# FMC_HPC_400.net
KiCad netlist of a schematic drawn in Altium Designer
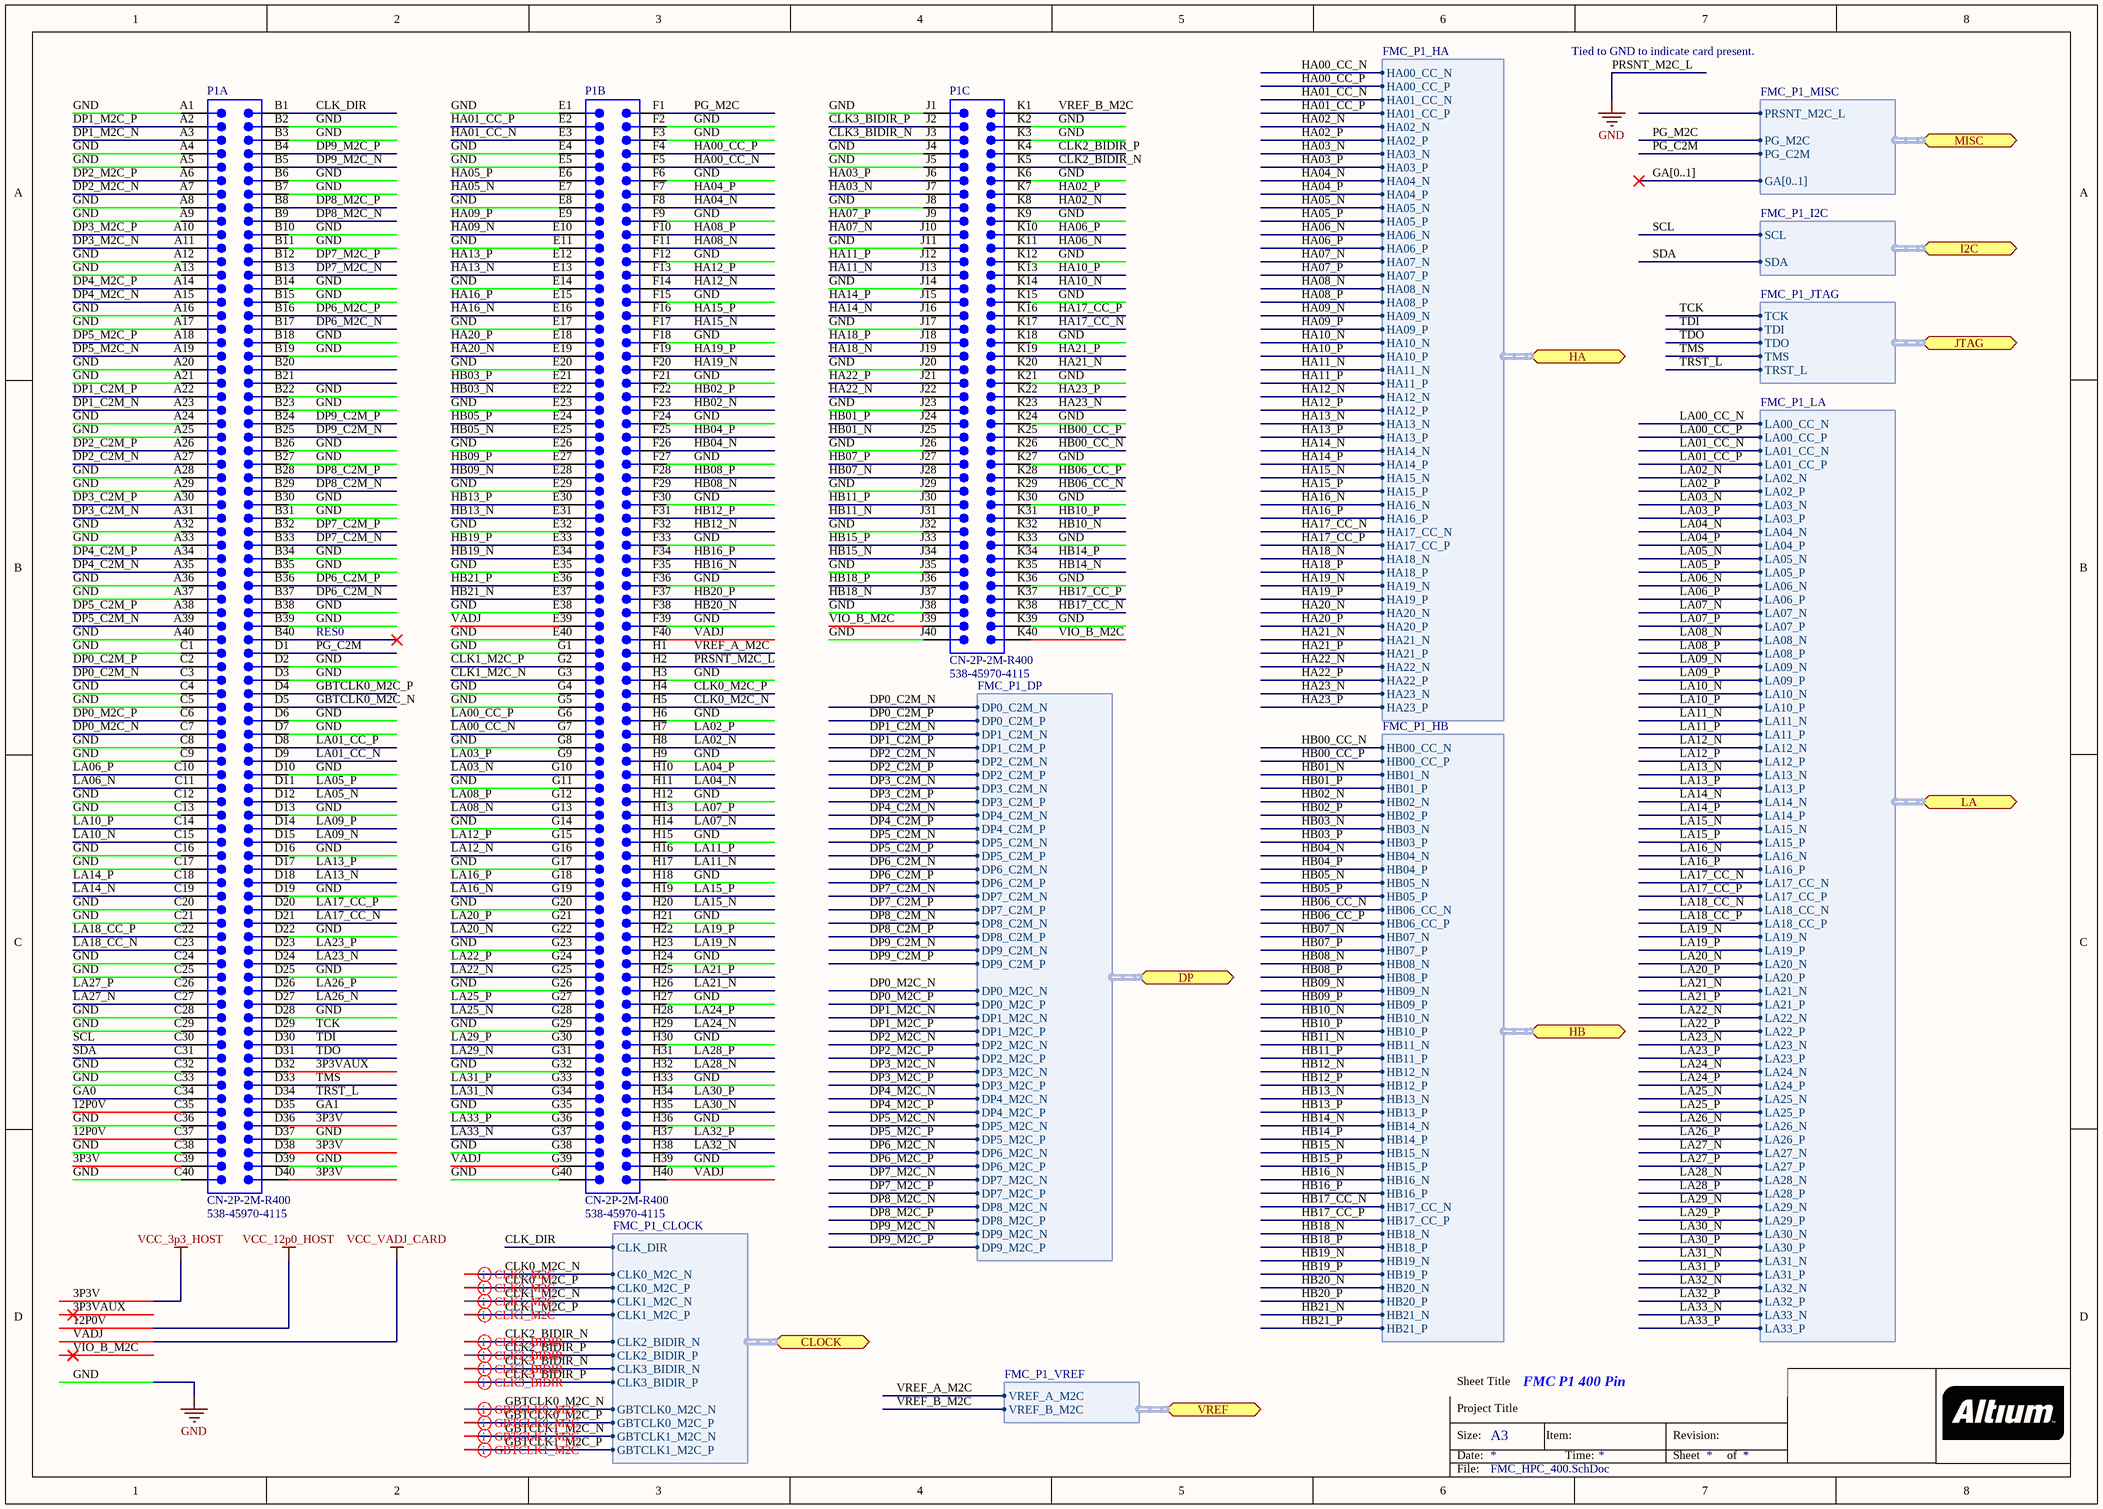
[diagram p0: FMC_HPC_400.SchDoc]

(export (version "E")
  (design (tool "Eeschema 10.0.6"))
  (components
    (comp (ref "P1")
      (value "CN-2P-2M-R400")
      (footprint "BTB-SM1-27-2V400M")
      (description "Board-to-Board Connector, Vertical, 10-Row, Pitch 1.27mm, 400-Position")
      (fields
        (field (name "MANUFACTURER") "Molex")
        (field (name "MANUFACTURER PART NUMBER") "45970-4115")
        (field (name "SUPPLIER PART NUMBER 1") "538-45970-4115")
      )
      (libsource (lib "RNG_Parts") (part "CN-2P-2M-R400"))
    )
  )
  (nets
    (net (code "10") (name "/3P3VAUX") (class "Default")
      (node (ref "P1") (pin "D32") (pinfunction "D32_D32") (pintype "passive+no_connect"))
    )
    (net (code "11") (name "/CLK0_M2C_N") (class "Default")
      (node (ref "P1") (pin "H5") (pinfunction "H5_H5") (pintype "passive"))
    )
    (net (code "12") (name "/CLK0_M2C_P") (class "Default")
      (node (ref "P1") (pin "H4") (pinfunction "H4_H4") (pintype "passive"))
    )
    (net (code "13") (name "/CLK1_M2C_N") (class "Default")
      (node (ref "P1") (pin "G3") (pinfunction "G3_G3") (pintype "passive"))
    )
    (net (code "14") (name "/CLK1_M2C_P") (class "Default")
      (node (ref "P1") (pin "G2") (pinfunction "G2_G2") (pintype "passive"))
    )
    (net (code "15") (name "/CLK2_BIDIR_N") (class "Default")
      (node (ref "P1") (pin "K5") (pinfunction "K5_K5") (pintype "passive"))
    )
    (net (code "16") (name "/CLK2_BIDIR_P") (class "Default")
      (node (ref "P1") (pin "K4") (pinfunction "K4_K4") (pintype "passive"))
    )
    (net (code "17") (name "/CLK3_BIDIR_N") (class "Default")
      (node (ref "P1") (pin "J3") (pinfunction "J3_J3") (pintype "passive"))
    )
    (net (code "18") (name "/CLK3_BIDIR_P") (class "Default")
      (node (ref "P1") (pin "J2") (pinfunction "J2_J2") (pintype "passive"))
    )
    (net (code "19") (name "/CLK_DIR") (class "Default")
      (node (ref "P1") (pin "B1") (pinfunction "B1_B1") (pintype "passive"))
    )
    (net (code "20") (name "/DP0_C2M_N") (class "Default")
      (node (ref "P1") (pin "C3") (pinfunction "C3_C3") (pintype "passive"))
    )
    (net (code "21") (name "/DP0_C2M_P") (class "Default")
      (node (ref "P1") (pin "C2") (pinfunction "C2_C2") (pintype "passive"))
    )
    (net (code "22") (name "/DP0_M2C_N") (class "Default")
      (node (ref "P1") (pin "C7") (pinfunction "C7_C7") (pintype "passive"))
    )
    (net (code "23") (name "/DP0_M2C_P") (class "Default")
      (node (ref "P1") (pin "C6") (pinfunction "C6_C6") (pintype "passive"))
    )
    (net (code "24") (name "/DP1_C2M_N") (class "Default")
      (node (ref "P1") (pin "A23") (pinfunction "A23_A23") (pintype "passive"))
    )
    (net (code "25") (name "/DP1_C2M_P") (class "Default")
      (node (ref "P1") (pin "A22") (pinfunction "A22_A22") (pintype "passive"))
    )
    (net (code "26") (name "/DP1_M2C_N") (class "Default")
      (node (ref "P1") (pin "A3") (pinfunction "A3_A3") (pintype "passive"))
    )
    (net (code "27") (name "/DP1_M2C_P") (class "Default")
      (node (ref "P1") (pin "A2") (pinfunction "A2_A2") (pintype "passive"))
    )
    (net (code "28") (name "/DP2_C2M_N") (class "Default")
      (node (ref "P1") (pin "A27") (pinfunction "A27_A27") (pintype "passive"))
    )
    (net (code "29") (name "/DP2_C2M_P") (class "Default")
      (node (ref "P1") (pin "A26") (pinfunction "A26_A26") (pintype "passive"))
    )
    (net (code "30") (name "/DP2_M2C_N") (class "Default")
      (node (ref "P1") (pin "A7") (pinfunction "A7_A7") (pintype "passive"))
    )
    (net (code "31") (name "/DP2_M2C_P") (class "Default")
      (node (ref "P1") (pin "A6") (pinfunction "A6_A6") (pintype "passive"))
    )
    (net (code "32") (name "/DP3_C2M_N") (class "Default")
      (node (ref "P1") (pin "A31") (pinfunction "A31_A31") (pintype "passive"))
    )
    (net (code "33") (name "/DP3_C2M_P") (class "Default")
      (node (ref "P1") (pin "A30") (pinfunction "A30_A30") (pintype "passive"))
    )
    (net (code "34") (name "/DP3_M2C_N") (class "Default")
      (node (ref "P1") (pin "A11") (pinfunction "A11_A11") (pintype "passive"))
    )
    (net (code "35") (name "/DP3_M2C_P") (class "Default")
      (node (ref "P1") (pin "A10") (pinfunction "A10_A10") (pintype "passive"))
    )
    (net (code "36") (name "/DP4_C2M_N") (class "Default")
      (node (ref "P1") (pin "A35") (pinfunction "A35_A35") (pintype "passive"))
    )
    (net (code "37") (name "/DP4_C2M_P") (class "Default")
      (node (ref "P1") (pin "A34") (pinfunction "A34_A34") (pintype "passive"))
    )
    (net (code "38") (name "/DP4_M2C_N") (class "Default")
      (node (ref "P1") (pin "A15") (pinfunction "A15_A15") (pintype "passive"))
    )
    (net (code "39") (name "/DP4_M2C_P") (class "Default")
      (node (ref "P1") (pin "A14") (pinfunction "A14_A14") (pintype "passive"))
    )
    (net (code "40") (name "/DP5_C2M_N") (class "Default")
      (node (ref "P1") (pin "A39") (pinfunction "A39_A39") (pintype "passive"))
    )
    (net (code "41") (name "/DP5_C2M_P") (class "Default")
      (node (ref "P1") (pin "A38") (pinfunction "A38_A38") (pintype "passive"))
    )
    (net (code "42") (name "/DP5_M2C_N") (class "Default")
      (node (ref "P1") (pin "A19") (pinfunction "A19_A19") (pintype "passive"))
    )
    (net (code "43") (name "/DP5_M2C_P") (class "Default")
      (node (ref "P1") (pin "A18") (pinfunction "A18_A18") (pintype "passive"))
    )
    (net (code "44") (name "/DP6_C2M_N") (class "Default")
      (node (ref "P1") (pin "B37") (pinfunction "B37_B37") (pintype "passive"))
    )
    (net (code "45") (name "/DP6_C2M_P") (class "Default")
      (node (ref "P1") (pin "B36") (pinfunction "B36_B36") (pintype "passive"))
    )
    (net (code "46") (name "/DP6_M2C_N") (class "Default")
      (node (ref "P1") (pin "B17") (pinfunction "B17_B17") (pintype "passive"))
    )
    (net (code "47") (name "/DP6_M2C_P") (class "Default")
      (node (ref "P1") (pin "B16") (pinfunction "B16_B16") (pintype "passive"))
    )
    (net (code "48") (name "/DP7_C2M_N") (class "Default")
      (node (ref "P1") (pin "B33") (pinfunction "B33_B33") (pintype "passive"))
    )
    (net (code "49") (name "/DP7_C2M_P") (class "Default")
      (node (ref "P1") (pin "B32") (pinfunction "B32_B32") (pintype "passive"))
    )
    (net (code "50") (name "/DP7_M2C_N") (class "Default")
      (node (ref "P1") (pin "B13") (pinfunction "B13_B13") (pintype "passive"))
    )
    (net (code "51") (name "/DP7_M2C_P") (class "Default")
      (node (ref "P1") (pin "B12") (pinfunction "B12_B12") (pintype "passive"))
    )
    (net (code "52") (name "/DP8_C2M_N") (class "Default")
      (node (ref "P1") (pin "B29") (pinfunction "B29_B29") (pintype "passive"))
    )
    (net (code "53") (name "/DP8_C2M_P") (class "Default")
      (node (ref "P1") (pin "B28") (pinfunction "B28_B28") (pintype "passive"))
    )
    (net (code "54") (name "/DP8_M2C_N") (class "Default")
      (node (ref "P1") (pin "B9") (pinfunction "B9_B9") (pintype "passive"))
    )
    (net (code "55") (name "/DP8_M2C_P") (class "Default")
      (node (ref "P1") (pin "B8") (pinfunction "B8_B8") (pintype "passive"))
    )
    (net (code "56") (name "/DP9_C2M_N") (class "Default")
      (node (ref "P1") (pin "B25") (pinfunction "B25_B25") (pintype "passive"))
    )
    (net (code "57") (name "/DP9_C2M_P") (class "Default")
      (node (ref "P1") (pin "B24") (pinfunction "B24_B24") (pintype "passive"))
    )
    (net (code "58") (name "/DP9_M2C_N") (class "Default")
      (node (ref "P1") (pin "B5") (pinfunction "B5_B5") (pintype "passive"))
    )
    (net (code "59") (name "/DP9_M2C_P") (class "Default")
      (node (ref "P1") (pin "B4") (pinfunction "B4_B4") (pintype "passive"))
    )
    (net (code "60") (name "/GA0") (class "Default")
      (node (ref "P1") (pin "C34") (pinfunction "C34_C34") (pintype "passive"))
    )
    (net (code "61") (name "/GA1") (class "Default")
      (node (ref "P1") (pin "D35") (pinfunction "D35_D35") (pintype "passive"))
    )
    (net (code "62") (name "/GBTCLK0_M2C_N") (class "Default")
      (node (ref "P1") (pin "D5") (pinfunction "D5_D5") (pintype "passive"))
    )
    (net (code "63") (name "/GBTCLK0_M2C_P") (class "Default")
      (node (ref "P1") (pin "D4") (pinfunction "D4_D4") (pintype "passive"))
    )
    (net (code "66") (name "/HA00_CC_N") (class "Default")
      (node (ref "P1") (pin "F5") (pinfunction "F5_F5") (pintype "passive"))
    )
    (net (code "67") (name "/HA00_CC_P") (class "Default")
      (node (ref "P1") (pin "F4") (pinfunction "F4_F4") (pintype "passive"))
    )
    (net (code "68") (name "/HA01_CC_N") (class "Default")
      (node (ref "P1") (pin "E3") (pinfunction "E3_E3") (pintype "passive"))
    )
    (net (code "69") (name "/HA01_CC_P") (class "Default")
      (node (ref "P1") (pin "E2") (pinfunction "E2_E2") (pintype "passive"))
    )
    (net (code "70") (name "/HA02_N") (class "Default")
      (node (ref "P1") (pin "K8") (pinfunction "K8_K8") (pintype "passive"))
    )
    (net (code "71") (name "/HA02_P") (class "Default")
      (node (ref "P1") (pin "K7") (pinfunction "K7_K7") (pintype "passive"))
    )
    (net (code "72") (name "/HA03_N") (class "Default")
      (node (ref "P1") (pin "J7") (pinfunction "J7_J7") (pintype "passive"))
    )
    (net (code "73") (name "/HA03_P") (class "Default")
      (node (ref "P1") (pin "J6") (pinfunction "J6_J6") (pintype "passive"))
    )
    (net (code "74") (name "/HA04_N") (class "Default")
      (node (ref "P1") (pin "F8") (pinfunction "F8_F8") (pintype "passive"))
    )
    (net (code "75") (name "/HA04_P") (class "Default")
      (node (ref "P1") (pin "F7") (pinfunction "F7_F7") (pintype "passive"))
    )
    (net (code "76") (name "/HA05_N") (class "Default")
      (node (ref "P1") (pin "E7") (pinfunction "E7_E7") (pintype "passive"))
    )
    (net (code "77") (name "/HA05_P") (class "Default")
      (node (ref "P1") (pin "E6") (pinfunction "E6_E6") (pintype "passive"))
    )
    (net (code "78") (name "/HA06_N") (class "Default")
      (node (ref "P1") (pin "K11") (pinfunction "K11_K11") (pintype "passive"))
    )
    (net (code "79") (name "/HA06_P") (class "Default")
      (node (ref "P1") (pin "K10") (pinfunction "K10_K10") (pintype "passive"))
    )
    (net (code "80") (name "/HA07_N") (class "Default")
      (node (ref "P1") (pin "J10") (pinfunction "J10_J10") (pintype "passive"))
    )
    (net (code "81") (name "/HA07_P") (class "Default")
      (node (ref "P1") (pin "J9") (pinfunction "J9_J9") (pintype "passive"))
    )
    (net (code "82") (name "/HA08_N") (class "Default")
      (node (ref "P1") (pin "F11") (pinfunction "F11_F11") (pintype "passive"))
    )
    (net (code "83") (name "/HA08_P") (class "Default")
      (node (ref "P1") (pin "F10") (pinfunction "F10_F10") (pintype "passive"))
    )
    (net (code "84") (name "/HA09_N") (class "Default")
      (node (ref "P1") (pin "E10") (pinfunction "E10_E10") (pintype "passive"))
    )
    (net (code "85") (name "/HA09_P") (class "Default")
      (node (ref "P1") (pin "E9") (pinfunction "E9_E9") (pintype "passive"))
    )
    (net (code "86") (name "/HA10_N") (class "Default")
      (node (ref "P1") (pin "K14") (pinfunction "K14_K14") (pintype "passive"))
    )
    (net (code "87") (name "/HA10_P") (class "Default")
      (node (ref "P1") (pin "K13") (pinfunction "K13_K13") (pintype "passive"))
    )
    (net (code "88") (name "/HA11_N") (class "Default")
      (node (ref "P1") (pin "J13") (pinfunction "J13_J13") (pintype "passive"))
    )
    (net (code "89") (name "/HA11_P") (class "Default")
      (node (ref "P1") (pin "J12") (pinfunction "J12_J12") (pintype "passive"))
    )
    (net (code "90") (name "/HA12_N") (class "Default")
      (node (ref "P1") (pin "F14") (pinfunction "F14_F14") (pintype "passive"))
    )
    (net (code "91") (name "/HA12_P") (class "Default")
      (node (ref "P1") (pin "F13") (pinfunction "F13_F13") (pintype "passive"))
    )
    (net (code "92") (name "/HA13_N") (class "Default")
      (node (ref "P1") (pin "E13") (pinfunction "E13_E13") (pintype "passive"))
    )
    (net (code "93") (name "/HA13_P") (class "Default")
      (node (ref "P1") (pin "E12") (pinfunction "E12_E12") (pintype "passive"))
    )
    (net (code "94") (name "/HA14_N") (class "Default")
      (node (ref "P1") (pin "J16") (pinfunction "J16_J16") (pintype "passive"))
    )
    (net (code "95") (name "/HA14_P") (class "Default")
      (node (ref "P1") (pin "J15") (pinfunction "J15_J15") (pintype "passive"))
    )
    (net (code "96") (name "/HA15_N") (class "Default")
      (node (ref "P1") (pin "F17") (pinfunction "F17_F17") (pintype "passive"))
    )
    (net (code "97") (name "/HA15_P") (class "Default")
      (node (ref "P1") (pin "F16") (pinfunction "F16_F16") (pintype "passive"))
    )
    (net (code "98") (name "/HA16_N") (class "Default")
      (node (ref "P1") (pin "E16") (pinfunction "E16_E16") (pintype "passive"))
    )
    (net (code "99") (name "/HA16_P") (class "Default")
      (node (ref "P1") (pin "E15") (pinfunction "E15_E15") (pintype "passive"))
    )
    (net (code "100") (name "/HA17_CC_N") (class "Default")
      (node (ref "P1") (pin "K17") (pinfunction "K17_K17") (pintype "passive"))
    )
    (net (code "101") (name "/HA17_CC_P") (class "Default")
      (node (ref "P1") (pin "K16") (pinfunction "K16_K16") (pintype "passive"))
    )
    (net (code "102") (name "/HA18_N") (class "Default")
      (node (ref "P1") (pin "J19") (pinfunction "J19_J19") (pintype "passive"))
    )
    (net (code "103") (name "/HA18_P") (class "Default")
      (node (ref "P1") (pin "J18") (pinfunction "J18_J18") (pintype "passive"))
    )
    (net (code "104") (name "/HA19_N") (class "Default")
      (node (ref "P1") (pin "F20") (pinfunction "F20_F20") (pintype "passive"))
    )
    (net (code "105") (name "/HA19_P") (class "Default")
      (node (ref "P1") (pin "F19") (pinfunction "F19_F19") (pintype "passive"))
    )
    (net (code "106") (name "/HA20_N") (class "Default")
      (node (ref "P1") (pin "E19") (pinfunction "E19_E19") (pintype "passive"))
    )
    (net (code "107") (name "/HA20_P") (class "Default")
      (node (ref "P1") (pin "E18") (pinfunction "E18_E18") (pintype "passive"))
    )
    (net (code "108") (name "/HA21_N") (class "Default")
      (node (ref "P1") (pin "K20") (pinfunction "K20_K20") (pintype "passive"))
    )
    (net (code "109") (name "/HA21_P") (class "Default")
      (node (ref "P1") (pin "K19") (pinfunction "K19_K19") (pintype "passive"))
    )
    (net (code "110") (name "/HA22_N") (class "Default")
      (node (ref "P1") (pin "J22") (pinfunction "J22_J22") (pintype "passive"))
    )
    (net (code "111") (name "/HA22_P") (class "Default")
      (node (ref "P1") (pin "J21") (pinfunction "J21_J21") (pintype "passive"))
    )
    (net (code "112") (name "/HA23_N") (class "Default")
      (node (ref "P1") (pin "K23") (pinfunction "K23_K23") (pintype "passive"))
    )
    (net (code "113") (name "/HA23_P") (class "Default")
      (node (ref "P1") (pin "K22") (pinfunction "K22_K22") (pintype "passive"))
    )
    (net (code "114") (name "/HB00_CC_N") (class "Default")
      (node (ref "P1") (pin "K26") (pinfunction "K26_K26") (pintype "passive"))
    )
    (net (code "115") (name "/HB00_CC_P") (class "Default")
      (node (ref "P1") (pin "K25") (pinfunction "K25_K25") (pintype "passive"))
    )
    (net (code "116") (name "/HB01_N") (class "Default")
      (node (ref "P1") (pin "J25") (pinfunction "J25_J25") (pintype "passive"))
    )
    (net (code "117") (name "/HB01_P") (class "Default")
      (node (ref "P1") (pin "J24") (pinfunction "J24_J24") (pintype "passive"))
    )
    (net (code "118") (name "/HB02_N") (class "Default")
      (node (ref "P1") (pin "F23") (pinfunction "F23_F23") (pintype "passive"))
    )
    (net (code "119") (name "/HB02_P") (class "Default")
      (node (ref "P1") (pin "F22") (pinfunction "F22_F22") (pintype "passive"))
    )
    (net (code "120") (name "/HB03_N") (class "Default")
      (node (ref "P1") (pin "E22") (pinfunction "E22_E22") (pintype "passive"))
    )
    (net (code "121") (name "/HB03_P") (class "Default")
      (node (ref "P1") (pin "E21") (pinfunction "E21_E21") (pintype "passive"))
    )
    (net (code "122") (name "/HB04_N") (class "Default")
      (node (ref "P1") (pin "F26") (pinfunction "F26_F26") (pintype "passive"))
    )
    (net (code "123") (name "/HB04_P") (class "Default")
      (node (ref "P1") (pin "F25") (pinfunction "F25_F25") (pintype "passive"))
    )
    (net (code "124") (name "/HB05_N") (class "Default")
      (node (ref "P1") (pin "E25") (pinfunction "E25_E25") (pintype "passive"))
    )
    (net (code "125") (name "/HB05_P") (class "Default")
      (node (ref "P1") (pin "E24") (pinfunction "E24_E24") (pintype "passive"))
    )
    (net (code "126") (name "/HB06_CC_N") (class "Default")
      (node (ref "P1") (pin "K29") (pinfunction "K29_K29") (pintype "passive"))
    )
    (net (code "127") (name "/HB06_CC_P") (class "Default")
      (node (ref "P1") (pin "K28") (pinfunction "K28_K28") (pintype "passive"))
    )
    (net (code "128") (name "/HB07_N") (class "Default")
      (node (ref "P1") (pin "J28") (pinfunction "J28_J28") (pintype "passive"))
    )
    (net (code "129") (name "/HB07_P") (class "Default")
      (node (ref "P1") (pin "J27") (pinfunction "J27_J27") (pintype "passive"))
    )
    (net (code "130") (name "/HB08_N") (class "Default")
      (node (ref "P1") (pin "F29") (pinfunction "F29_F29") (pintype "passive"))
    )
    (net (code "131") (name "/HB08_P") (class "Default")
      (node (ref "P1") (pin "F28") (pinfunction "F28_F28") (pintype "passive"))
    )
    (net (code "132") (name "/HB09_N") (class "Default")
      (node (ref "P1") (pin "E28") (pinfunction "E28_E28") (pintype "passive"))
    )
    (net (code "133") (name "/HB09_P") (class "Default")
      (node (ref "P1") (pin "E27") (pinfunction "E27_E27") (pintype "passive"))
    )
    (net (code "134") (name "/HB10_N") (class "Default")
      (node (ref "P1") (pin "K32") (pinfunction "K32_K32") (pintype "passive"))
    )
    (net (code "135") (name "/HB10_P") (class "Default")
      (node (ref "P1") (pin "K31") (pinfunction "K31_K31") (pintype "passive"))
    )
    (net (code "136") (name "/HB11_N") (class "Default")
      (node (ref "P1") (pin "J31") (pinfunction "J31_J31") (pintype "passive"))
    )
    (net (code "137") (name "/HB11_P") (class "Default")
      (node (ref "P1") (pin "J30") (pinfunction "J30_J30") (pintype "passive"))
    )
    (net (code "138") (name "/HB12_N") (class "Default")
      (node (ref "P1") (pin "F32") (pinfunction "F32_F32") (pintype "passive"))
    )
    (net (code "139") (name "/HB12_P") (class "Default")
      (node (ref "P1") (pin "F31") (pinfunction "F31_F31") (pintype "passive"))
    )
    (net (code "140") (name "/HB13_N") (class "Default")
      (node (ref "P1") (pin "E31") (pinfunction "E31_E31") (pintype "passive"))
    )
    (net (code "141") (name "/HB13_P") (class "Default")
      (node (ref "P1") (pin "E30") (pinfunction "E30_E30") (pintype "passive"))
    )
    (net (code "142") (name "/HB14_N") (class "Default")
      (node (ref "P1") (pin "K35") (pinfunction "K35_K35") (pintype "passive"))
    )
    (net (code "143") (name "/HB14_P") (class "Default")
      (node (ref "P1") (pin "K34") (pinfunction "K34_K34") (pintype "passive"))
    )
    (net (code "144") (name "/HB15_N") (class "Default")
      (node (ref "P1") (pin "J34") (pinfunction "J34_J34") (pintype "passive"))
    )
    (net (code "145") (name "/HB15_P") (class "Default")
      (node (ref "P1") (pin "J33") (pinfunction "J33_J33") (pintype "passive"))
    )
    (net (code "146") (name "/HB16_N") (class "Default")
      (node (ref "P1") (pin "F35") (pinfunction "F35_F35") (pintype "passive"))
    )
    (net (code "147") (name "/HB16_P") (class "Default")
      (node (ref "P1") (pin "F34") (pinfunction "F34_F34") (pintype "passive"))
    )
    (net (code "148") (name "/HB17_CC_N") (class "Default")
      (node (ref "P1") (pin "K38") (pinfunction "K38_K38") (pintype "passive"))
    )
    (net (code "149") (name "/HB17_CC_P") (class "Default")
      (node (ref "P1") (pin "K37") (pinfunction "K37_K37") (pintype "passive"))
    )
    (net (code "150") (name "/HB18_N") (class "Default")
      (node (ref "P1") (pin "J37") (pinfunction "J37_J37") (pintype "passive"))
    )
    (net (code "151") (name "/HB18_P") (class "Default")
      (node (ref "P1") (pin "J36") (pinfunction "J36_J36") (pintype "passive"))
    )
    (net (code "152") (name "/HB19_N") (class "Default")
      (node (ref "P1") (pin "E34") (pinfunction "E34_E34") (pintype "passive"))
    )
    (net (code "153") (name "/HB19_P") (class "Default")
      (node (ref "P1") (pin "E33") (pinfunction "E33_E33") (pintype "passive"))
    )
    (net (code "154") (name "/HB20_N") (class "Default")
      (node (ref "P1") (pin "F38") (pinfunction "F38_F38") (pintype "passive"))
    )
    (net (code "155") (name "/HB20_P") (class "Default")
      (node (ref "P1") (pin "F37") (pinfunction "F37_F37") (pintype "passive"))
    )
    (net (code "156") (name "/HB21_N") (class "Default")
      (node (ref "P1") (pin "E37") (pinfunction "E37_E37") (pintype "passive"))
    )
    (net (code "157") (name "/HB21_P") (class "Default")
      (node (ref "P1") (pin "E36") (pinfunction "E36_E36") (pintype "passive"))
    )
    (net (code "158") (name "/LA00_CC_N") (class "Default")
      (node (ref "P1") (pin "G7") (pinfunction "G7_G7") (pintype "passive"))
    )
    (net (code "159") (name "/LA00_CC_P") (class "Default")
      (node (ref "P1") (pin "G6") (pinfunction "G6_G6") (pintype "passive"))
    )
    (net (code "160") (name "/LA01_CC_N") (class "Default")
      (node (ref "P1") (pin "D9") (pinfunction "D9_D9") (pintype "passive"))
    )
    (net (code "161") (name "/LA01_CC_P") (class "Default")
      (node (ref "P1") (pin "D8") (pinfunction "D8_D8") (pintype "passive"))
    )
    (net (code "162") (name "/LA02_N") (class "Default")
      (node (ref "P1") (pin "H8") (pinfunction "H8_H8") (pintype "passive"))
    )
    (net (code "163") (name "/LA02_P") (class "Default")
      (node (ref "P1") (pin "H7") (pinfunction "H7_H7") (pintype "passive"))
    )
    (net (code "164") (name "/LA03_N") (class "Default")
      (node (ref "P1") (pin "G10") (pinfunction "G10_G10") (pintype "passive"))
    )
    (net (code "165") (name "/LA03_P") (class "Default")
      (node (ref "P1") (pin "G9") (pinfunction "G9_G9") (pintype "passive"))
    )
    (net (code "166") (name "/LA04_N") (class "Default")
      (node (ref "P1") (pin "H11") (pinfunction "H11_H11") (pintype "passive"))
    )
    (net (code "167") (name "/LA04_P") (class "Default")
      (node (ref "P1") (pin "H10") (pinfunction "H10_H10") (pintype "passive"))
    )
    (net (code "168") (name "/LA05_N") (class "Default")
      (node (ref "P1") (pin "D12") (pinfunction "D12_D12") (pintype "passive"))
    )
    (net (code "169") (name "/LA05_P") (class "Default")
      (node (ref "P1") (pin "D11") (pinfunction "D11_D11") (pintype "passive"))
    )
    (net (code "170") (name "/LA06_N") (class "Default")
      (node (ref "P1") (pin "C11") (pinfunction "C11_C11") (pintype "passive"))
    )
    (net (code "171") (name "/LA06_P") (class "Default")
      (node (ref "P1") (pin "C10") (pinfunction "C10_C10") (pintype "passive"))
    )
    (net (code "172") (name "/LA07_N") (class "Default")
      (node (ref "P1") (pin "H14") (pinfunction "H14_H14") (pintype "passive"))
    )
    (net (code "173") (name "/LA07_P") (class "Default")
      (node (ref "P1") (pin "H13") (pinfunction "H13_H13") (pintype "passive"))
    )
    (net (code "174") (name "/LA08_N") (class "Default")
      (node (ref "P1") (pin "G13") (pinfunction "G13_G13") (pintype "passive"))
    )
    (net (code "175") (name "/LA08_P") (class "Default")
      (node (ref "P1") (pin "G12") (pinfunction "G12_G12") (pintype "passive"))
    )
    (net (code "176") (name "/LA09_N") (class "Default")
      (node (ref "P1") (pin "D15") (pinfunction "D15_D15") (pintype "passive"))
    )
    (net (code "177") (name "/LA09_P") (class "Default")
      (node (ref "P1") (pin "D14") (pinfunction "D14_D14") (pintype "passive"))
    )
    (net (code "178") (name "/LA10_N") (class "Default")
      (node (ref "P1") (pin "C15") (pinfunction "C15_C15") (pintype "passive"))
    )
    (net (code "179") (name "/LA10_P") (class "Default")
      (node (ref "P1") (pin "C14") (pinfunction "C14_C14") (pintype "passive"))
    )
    (net (code "180") (name "/LA11_N") (class "Default")
      (node (ref "P1") (pin "H17") (pinfunction "H17_H17") (pintype "passive"))
    )
    (net (code "181") (name "/LA11_P") (class "Default")
      (node (ref "P1") (pin "H16") (pinfunction "H16_H16") (pintype "passive"))
    )
    (net (code "182") (name "/LA12_N") (class "Default")
      (node (ref "P1") (pin "G16") (pinfunction "G16_G16") (pintype "passive"))
    )
    (net (code "183") (name "/LA12_P") (class "Default")
      (node (ref "P1") (pin "G15") (pinfunction "G15_G15") (pintype "passive"))
    )
    (net (code "184") (name "/LA13_N") (class "Default")
      (node (ref "P1") (pin "D18") (pinfunction "D18_D18") (pintype "passive"))
    )
    (net (code "185") (name "/LA13_P") (class "Default")
      (node (ref "P1") (pin "D17") (pinfunction "D17_D17") (pintype "passive"))
    )
    (net (code "186") (name "/LA14_N") (class "Default")
      (node (ref "P1") (pin "C19") (pinfunction "C19_C19") (pintype "passive"))
    )
    (net (code "187") (name "/LA14_P") (class "Default")
      (node (ref "P1") (pin "C18") (pinfunction "C18_C18") (pintype "passive"))
    )
    (net (code "188") (name "/LA15_N") (class "Default")
      (node (ref "P1") (pin "H20") (pinfunction "H20_H20") (pintype "passive"))
    )
    (net (code "189") (name "/LA15_P") (class "Default")
      (node (ref "P1") (pin "H19") (pinfunction "H19_H19") (pintype "passive"))
    )
    (net (code "190") (name "/LA16_N") (class "Default")
      (node (ref "P1") (pin "G19") (pinfunction "G19_G19") (pintype "passive"))
    )
    (net (code "191") (name "/LA16_P") (class "Default")
      (node (ref "P1") (pin "G18") (pinfunction "G18_G18") (pintype "passive"))
    )
    (net (code "192") (name "/LA17_CC_N") (class "Default")
      (node (ref "P1") (pin "D21") (pinfunction "D21_D21") (pintype "passive"))
    )
    (net (code "193") (name "/LA17_CC_P") (class "Default")
      (node (ref "P1") (pin "D20") (pinfunction "D20_D20") (pintype "passive"))
    )
    (net (code "194") (name "/LA18_CC_N") (class "Default")
      (node (ref "P1") (pin "C23") (pinfunction "C23_C23") (pintype "passive"))
    )
    (net (code "195") (name "/LA18_CC_P") (class "Default")
      (node (ref "P1") (pin "C22") (pinfunction "C22_C22") (pintype "passive"))
    )
    (net (code "196") (name "/LA19_N") (class "Default")
      (node (ref "P1") (pin "H23") (pinfunction "H23_H23") (pintype "passive"))
    )
    (net (code "197") (name "/LA19_P") (class "Default")
      (node (ref "P1") (pin "H22") (pinfunction "H22_H22") (pintype "passive"))
    )
    (net (code "198") (name "/LA20_N") (class "Default")
      (node (ref "P1") (pin "G22") (pinfunction "G22_G22") (pintype "passive"))
    )
    (net (code "199") (name "/LA20_P") (class "Default")
      (node (ref "P1") (pin "G21") (pinfunction "G21_G21") (pintype "passive"))
    )
    (net (code "200") (name "/LA21_N") (class "Default")
      (node (ref "P1") (pin "H26") (pinfunction "H26_H26") (pintype "passive"))
    )
    (net (code "201") (name "/LA21_P") (class "Default")
      (node (ref "P1") (pin "H25") (pinfunction "H25_H25") (pintype "passive"))
    )
    (net (code "202") (name "/LA22_N") (class "Default")
      (node (ref "P1") (pin "G25") (pinfunction "G25_G25") (pintype "passive"))
    )
    (net (code "203") (name "/LA22_P") (class "Default")
      (node (ref "P1") (pin "G24") (pinfunction "G24_G24") (pintype "passive"))
    )
    (net (code "204") (name "/LA23_N") (class "Default")
      (node (ref "P1") (pin "D24") (pinfunction "D24_D24") (pintype "passive"))
    )
    (net (code "205") (name "/LA23_P") (class "Default")
      (node (ref "P1") (pin "D23") (pinfunction "D23_D23") (pintype "passive"))
    )
    (net (code "206") (name "/LA24_N") (class "Default")
      (node (ref "P1") (pin "H29") (pinfunction "H29_H29") (pintype "passive"))
    )
    (net (code "207") (name "/LA24_P") (class "Default")
      (node (ref "P1") (pin "H28") (pinfunction "H28_H28") (pintype "passive"))
    )
    (net (code "208") (name "/LA25_N") (class "Default")
      (node (ref "P1") (pin "G28") (pinfunction "G28_G28") (pintype "passive"))
    )
    (net (code "209") (name "/LA25_P") (class "Default")
      (node (ref "P1") (pin "G27") (pinfunction "G27_G27") (pintype "passive"))
    )
    (net (code "210") (name "/LA26_N") (class "Default")
      (node (ref "P1") (pin "D27") (pinfunction "D27_D27") (pintype "passive"))
    )
    (net (code "211") (name "/LA26_P") (class "Default")
      (node (ref "P1") (pin "D26") (pinfunction "D26_D26") (pintype "passive"))
    )
    (net (code "212") (name "/LA27_N") (class "Default")
      (node (ref "P1") (pin "C27") (pinfunction "C27_C27") (pintype "passive"))
    )
    (net (code "213") (name "/LA27_P") (class "Default")
      (node (ref "P1") (pin "C26") (pinfunction "C26_C26") (pintype "passive"))
    )
    (net (code "214") (name "/LA28_N") (class "Default")
      (node (ref "P1") (pin "H32") (pinfunction "H32_H32") (pintype "passive"))
    )
    (net (code "215") (name "/LA28_P") (class "Default")
      (node (ref "P1") (pin "H31") (pinfunction "H31_H31") (pintype "passive"))
    )
    (net (code "216") (name "/LA29_N") (class "Default")
      (node (ref "P1") (pin "G31") (pinfunction "G31_G31") (pintype "passive"))
    )
    (net (code "217") (name "/LA29_P") (class "Default")
      (node (ref "P1") (pin "G30") (pinfunction "G30_G30") (pintype "passive"))
    )
    (net (code "218") (name "/LA30_N") (class "Default")
      (node (ref "P1") (pin "H35") (pinfunction "H35_H35") (pintype "passive"))
    )
    (net (code "219") (name "/LA30_P") (class "Default")
      (node (ref "P1") (pin "H34") (pinfunction "H34_H34") (pintype "passive"))
    )
    (net (code "220") (name "/LA31_N") (class "Default")
      (node (ref "P1") (pin "G34") (pinfunction "G34_G34") (pintype "passive"))
    )
    (net (code "221") (name "/LA31_P") (class "Default")
      (node (ref "P1") (pin "G33") (pinfunction "G33_G33") (pintype "passive"))
    )
    (net (code "222") (name "/LA32_N") (class "Default")
      (node (ref "P1") (pin "H38") (pinfunction "H38_H38") (pintype "passive"))
    )
    (net (code "223") (name "/LA32_P") (class "Default")
      (node (ref "P1") (pin "H37") (pinfunction "H37_H37") (pintype "passive"))
    )
    (net (code "224") (name "/LA33_N") (class "Default")
      (node (ref "P1") (pin "G37") (pinfunction "G37_G37") (pintype "passive"))
    )
    (net (code "225") (name "/LA33_P") (class "Default")
      (node (ref "P1") (pin "G36") (pinfunction "G36_G36") (pintype "passive"))
    )
    (net (code "227") (name "/PG_C2M") (class "Default")
      (node (ref "P1") (pin "D1") (pinfunction "D1_D1") (pintype "passive"))
    )
    (net (code "228") (name "/PG_M2C") (class "Default")
      (node (ref "P1") (pin "F1") (pinfunction "F1_F1") (pintype "passive"))
    )
    (net (code "229") (name "/SCL") (class "Default")
      (node (ref "P1") (pin "C30") (pinfunction "C30_C30") (pintype "passive"))
    )
    (net (code "230") (name "/SDA") (class "Default")
      (node (ref "P1") (pin "C31") (pinfunction "C31_C31") (pintype "passive"))
    )
    (net (code "231") (name "/TCK") (class "Default")
      (node (ref "P1") (pin "D29") (pinfunction "D29_D29") (pintype "passive"))
    )
    (net (code "232") (name "/TDI") (class "Default")
      (node (ref "P1") (pin "D30") (pinfunction "D30_D30") (pintype "passive"))
    )
    (net (code "233") (name "/TDO") (class "Default")
      (node (ref "P1") (pin "D31") (pinfunction "D31_D31") (pintype "passive"))
    )
    (net (code "234") (name "/TMS") (class "Default")
      (node (ref "P1") (pin "D33") (pinfunction "D33_D33") (pintype "passive"))
    )
    (net (code "235") (name "/TRST_L") (class "Default")
      (node (ref "P1") (pin "D34") (pinfunction "D34_D34") (pintype "passive"))
    )
    (net (code "236") (name "/VIO_B_M2C") (class "Default")
      (node (ref "P1") (pin "J39") (pinfunction "J39_J39") (pintype "passive"))
      (node (ref "P1") (pin "K40") (pinfunction "K40_K40") (pintype "passive"))
    )
    (net (code "237") (name "/VREF_A_M2C") (class "Default")
      (node (ref "P1") (pin "H1") (pinfunction "H1_H1") (pintype "passive"))
    )
    (net (code "238") (name "/VREF_B_M2C") (class "Default")
      (node (ref "P1") (pin "K1") (pinfunction "K1_K1") (pintype "passive"))
    )
    (net (code "248") (name "GND") (class "Default")
      (node (ref "P1") (pin "A1") (pinfunction "A1_A1") (pintype "passive"))
      (node (ref "P1") (pin "A12") (pinfunction "A12_A12") (pintype "passive"))
      (node (ref "P1") (pin "A13") (pinfunction "A13_A13") (pintype "passive"))
      (node (ref "P1") (pin "A16") (pinfunction "A16_A16") (pintype "passive"))
      (node (ref "P1") (pin "A17") (pinfunction "A17_A17") (pintype "passive"))
      (node (ref "P1") (pin "A20") (pinfunction "A20_A20") (pintype "passive"))
      (node (ref "P1") (pin "A21") (pinfunction "A21_A21") (pintype "passive"))
      (node (ref "P1") (pin "A24") (pinfunction "A24_A24") (pintype "passive"))
      (node (ref "P1") (pin "A25") (pinfunction "A25_A25") (pintype "passive"))
      (node (ref "P1") (pin "A28") (pinfunction "A28_A28") (pintype "passive"))
      (node (ref "P1") (pin "A29") (pinfunction "A29_A29") (pintype "passive"))
      (node (ref "P1") (pin "A32") (pinfunction "A32_A32") (pintype "passive"))
      (node (ref "P1") (pin "A33") (pinfunction "A33_A33") (pintype "passive"))
      (node (ref "P1") (pin "A36") (pinfunction "A36_A36") (pintype "passive"))
      (node (ref "P1") (pin "A37") (pinfunction "A37_A37") (pintype "passive"))
      (node (ref "P1") (pin "A4") (pinfunction "A4_A4") (pintype "passive"))
      (node (ref "P1") (pin "A40") (pinfunction "A40_A40") (pintype "passive"))
      (node (ref "P1") (pin "A5") (pinfunction "A5_A5") (pintype "passive"))
      (node (ref "P1") (pin "A8") (pinfunction "A8_A8") (pintype "passive"))
      (node (ref "P1") (pin "A9") (pinfunction "A9_A9") (pintype "passive"))
      (node (ref "P1") (pin "B10") (pinfunction "B10_B10") (pintype "passive"))
      (node (ref "P1") (pin "B11") (pinfunction "B11_B11") (pintype "passive"))
      (node (ref "P1") (pin "B14") (pinfunction "B14_B14") (pintype "passive"))
      (node (ref "P1") (pin "B15") (pinfunction "B15_B15") (pintype "passive"))
      (node (ref "P1") (pin "B18") (pinfunction "B18_B18") (pintype "passive"))
      (node (ref "P1") (pin "B19") (pinfunction "B19_B19") (pintype "passive"))
      (node (ref "P1") (pin "B2") (pinfunction "B2_B2") (pintype "passive"))
      (node (ref "P1") (pin "B22") (pinfunction "B22_B22") (pintype "passive"))
      (node (ref "P1") (pin "B23") (pinfunction "B23_B23") (pintype "passive"))
      (node (ref "P1") (pin "B26") (pinfunction "B26_B26") (pintype "passive"))
      (node (ref "P1") (pin "B27") (pinfunction "B27_B27") (pintype "passive"))
      (node (ref "P1") (pin "B3") (pinfunction "B3_B3") (pintype "passive"))
      (node (ref "P1") (pin "B30") (pinfunction "B30_B30") (pintype "passive"))
      (node (ref "P1") (pin "B31") (pinfunction "B31_B31") (pintype "passive"))
      (node (ref "P1") (pin "B34") (pinfunction "B34_B34") (pintype "passive"))
      (node (ref "P1") (pin "B35") (pinfunction "B35_B35") (pintype "passive"))
      (node (ref "P1") (pin "B38") (pinfunction "B38_B38") (pintype "passive"))
      (node (ref "P1") (pin "B39") (pinfunction "B39_B39") (pintype "passive"))
      (node (ref "P1") (pin "B6") (pinfunction "B6_B6") (pintype "passive"))
      (node (ref "P1") (pin "B7") (pinfunction "B7_B7") (pintype "passive"))
      (node (ref "P1") (pin "C1") (pinfunction "C1_C1") (pintype "passive"))
      (node (ref "P1") (pin "C12") (pinfunction "C12_C12") (pintype "passive"))
      (node (ref "P1") (pin "C13") (pinfunction "C13_C13") (pintype "passive"))
      (node (ref "P1") (pin "C16") (pinfunction "C16_C16") (pintype "passive"))
      (node (ref "P1") (pin "C17") (pinfunction "C17_C17") (pintype "passive"))
      (node (ref "P1") (pin "C20") (pinfunction "C20_C20") (pintype "passive"))
      (node (ref "P1") (pin "C21") (pinfunction "C21_C21") (pintype "passive"))
      (node (ref "P1") (pin "C24") (pinfunction "C24_C24") (pintype "passive"))
      (node (ref "P1") (pin "C25") (pinfunction "C25_C25") (pintype "passive"))
      (node (ref "P1") (pin "C28") (pinfunction "C28_C28") (pintype "passive"))
      (node (ref "P1") (pin "C29") (pinfunction "C29_C29") (pintype "passive"))
      (node (ref "P1") (pin "C32") (pinfunction "C32_C32") (pintype "passive"))
      (node (ref "P1") (pin "C33") (pinfunction "C33_C33") (pintype "passive"))
      (node (ref "P1") (pin "C36") (pinfunction "C36_C36") (pintype "passive"))
      (node (ref "P1") (pin "C38") (pinfunction "C38_C38") (pintype "passive"))
      (node (ref "P1") (pin "C4") (pinfunction "C4_C4") (pintype "passive"))
      (node (ref "P1") (pin "C40") (pinfunction "C40_C40") (pintype "passive"))
      (node (ref "P1") (pin "C5") (pinfunction "C5_C5") (pintype "passive"))
      (node (ref "P1") (pin "C8") (pinfunction "C8_C8") (pintype "passive"))
      (node (ref "P1") (pin "C9") (pinfunction "C9_C9") (pintype "passive"))
      (node (ref "P1") (pin "D10") (pinfunction "D10_D10") (pintype "passive"))
      (node (ref "P1") (pin "D13") (pinfunction "D13_D13") (pintype "passive"))
      (node (ref "P1") (pin "D16") (pinfunction "D16_D16") (pintype "passive"))
      (node (ref "P1") (pin "D19") (pinfunction "D19_D19") (pintype "passive"))
      (node (ref "P1") (pin "D2") (pinfunction "D2_D2") (pintype "passive"))
      (node (ref "P1") (pin "D22") (pinfunction "D22_D22") (pintype "passive"))
      (node (ref "P1") (pin "D25") (pinfunction "D25_D25") (pintype "passive"))
      (node (ref "P1") (pin "D28") (pinfunction "D28_D28") (pintype "passive"))
      (node (ref "P1") (pin "D3") (pinfunction "D3_D3") (pintype "passive"))
      (node (ref "P1") (pin "D37") (pinfunction "D37_D37") (pintype "passive"))
      (node (ref "P1") (pin "D39") (pinfunction "D39_D39") (pintype "passive"))
      (node (ref "P1") (pin "D6") (pinfunction "D6_D6") (pintype "passive"))
      (node (ref "P1") (pin "D7") (pinfunction "D7_D7") (pintype "passive"))
      (node (ref "P1") (pin "E1") (pinfunction "E1_E1") (pintype "passive"))
      (node (ref "P1") (pin "E11") (pinfunction "E11_E11") (pintype "passive"))
      (node (ref "P1") (pin "E14") (pinfunction "E14_E14") (pintype "passive"))
      (node (ref "P1") (pin "E17") (pinfunction "E17_E17") (pintype "passive"))
      (node (ref "P1") (pin "E20") (pinfunction "E20_E20") (pintype "passive"))
      (node (ref "P1") (pin "E23") (pinfunction "E23_E23") (pintype "passive"))
      (node (ref "P1") (pin "E26") (pinfunction "E26_E26") (pintype "passive"))
      (node (ref "P1") (pin "E29") (pinfunction "E29_E29") (pintype "passive"))
      (node (ref "P1") (pin "E32") (pinfunction "E32_E32") (pintype "passive"))
      (node (ref "P1") (pin "E35") (pinfunction "E35_E35") (pintype "passive"))
      (node (ref "P1") (pin "E38") (pinfunction "E38_E38") (pintype "passive"))
      (node (ref "P1") (pin "E4") (pinfunction "E4_E4") (pintype "passive"))
      (node (ref "P1") (pin "E40") (pinfunction "E40_E40") (pintype "passive"))
      (node (ref "P1") (pin "E5") (pinfunction "E5_E5") (pintype "passive"))
      (node (ref "P1") (pin "E8") (pinfunction "E8_E8") (pintype "passive"))
      (node (ref "P1") (pin "F12") (pinfunction "F12_F12") (pintype "passive"))
      (node (ref "P1") (pin "F15") (pinfunction "F15_F15") (pintype "passive"))
      (node (ref "P1") (pin "F18") (pinfunction "F18_F18") (pintype "passive"))
      (node (ref "P1") (pin "F2") (pinfunction "F2_F2") (pintype "passive"))
      (node (ref "P1") (pin "F21") (pinfunction "F21_F21") (pintype "passive"))
      (node (ref "P1") (pin "F24") (pinfunction "F24_F24") (pintype "passive"))
      (node (ref "P1") (pin "F27") (pinfunction "F27_F27") (pintype "passive"))
      (node (ref "P1") (pin "F3") (pinfunction "F3_F3") (pintype "passive"))
      (node (ref "P1") (pin "F30") (pinfunction "F30_F30") (pintype "passive"))
      (node (ref "P1") (pin "F33") (pinfunction "F33_F33") (pintype "passive"))
      (node (ref "P1") (pin "F36") (pinfunction "F36_F36") (pintype "passive"))
      (node (ref "P1") (pin "F39") (pinfunction "F39_F39") (pintype "passive"))
      (node (ref "P1") (pin "F6") (pinfunction "F6_F6") (pintype "passive"))
      (node (ref "P1") (pin "F9") (pinfunction "F9_F9") (pintype "passive"))
      (node (ref "P1") (pin "G1") (pinfunction "G1_G1") (pintype "passive"))
      (node (ref "P1") (pin "G11") (pinfunction "G11_G11") (pintype "passive"))
      (node (ref "P1") (pin "G14") (pinfunction "G14_G14") (pintype "passive"))
      (node (ref "P1") (pin "G17") (pinfunction "G17_G17") (pintype "passive"))
      (node (ref "P1") (pin "G20") (pinfunction "G20_G20") (pintype "passive"))
      (node (ref "P1") (pin "G23") (pinfunction "G23_G23") (pintype "passive"))
      (node (ref "P1") (pin "G26") (pinfunction "G26_G26") (pintype "passive"))
      (node (ref "P1") (pin "G29") (pinfunction "G29_G29") (pintype "passive"))
      (node (ref "P1") (pin "G32") (pinfunction "G32_G32") (pintype "passive"))
      (node (ref "P1") (pin "G35") (pinfunction "G35_G35") (pintype "passive"))
      (node (ref "P1") (pin "G38") (pinfunction "G38_G38") (pintype "passive"))
      (node (ref "P1") (pin "G4") (pinfunction "G4_G4") (pintype "passive"))
      (node (ref "P1") (pin "G40") (pinfunction "G40_G40") (pintype "passive"))
      (node (ref "P1") (pin "G5") (pinfunction "G5_G5") (pintype "passive"))
      (node (ref "P1") (pin "G8") (pinfunction "G8_G8") (pintype "passive"))
      (node (ref "P1") (pin "H12") (pinfunction "H12_H12") (pintype "passive"))
      (node (ref "P1") (pin "H15") (pinfunction "H15_H15") (pintype "passive"))
      (node (ref "P1") (pin "H18") (pinfunction "H18_H18") (pintype "passive"))
      (node (ref "P1") (pin "H2") (pinfunction "H2_H2") (pintype "passive"))
      (node (ref "P1") (pin "H21") (pinfunction "H21_H21") (pintype "passive"))
      (node (ref "P1") (pin "H24") (pinfunction "H24_H24") (pintype "passive"))
      (node (ref "P1") (pin "H27") (pinfunction "H27_H27") (pintype "passive"))
      (node (ref "P1") (pin "H3") (pinfunction "H3_H3") (pintype "passive"))
      (node (ref "P1") (pin "H30") (pinfunction "H30_H30") (pintype "passive"))
      (node (ref "P1") (pin "H33") (pinfunction "H33_H33") (pintype "passive"))
      (node (ref "P1") (pin "H36") (pinfunction "H36_H36") (pintype "passive"))
      (node (ref "P1") (pin "H39") (pinfunction "H39_H39") (pintype "passive"))
      (node (ref "P1") (pin "H6") (pinfunction "H6_H6") (pintype "passive"))
      (node (ref "P1") (pin "H9") (pinfunction "H9_H9") (pintype "passive"))
      (node (ref "P1") (pin "J1") (pinfunction "J1_J1") (pintype "passive"))
      (node (ref "P1") (pin "J11") (pinfunction "J11_J11") (pintype "passive"))
      (node (ref "P1") (pin "J14") (pinfunction "J14_J14") (pintype "passive"))
      (node (ref "P1") (pin "J17") (pinfunction "J17_J17") (pintype "passive"))
      (node (ref "P1") (pin "J20") (pinfunction "J20_J20") (pintype "passive"))
      (node (ref "P1") (pin "J23") (pinfunction "J23_J23") (pintype "passive"))
      (node (ref "P1") (pin "J26") (pinfunction "J26_J26") (pintype "passive"))
      (node (ref "P1") (pin "J29") (pinfunction "J29_J29") (pintype "passive"))
      (node (ref "P1") (pin "J32") (pinfunction "J32_J32") (pintype "passive"))
      (node (ref "P1") (pin "J35") (pinfunction "J35_J35") (pintype "passive"))
      (node (ref "P1") (pin "J38") (pinfunction "J38_J38") (pintype "passive"))
      (node (ref "P1") (pin "J4") (pinfunction "J4_J4") (pintype "passive"))
      (node (ref "P1") (pin "J40") (pinfunction "J40_J40") (pintype "passive"))
      (node (ref "P1") (pin "J5") (pinfunction "J5_J5") (pintype "passive"))
      (node (ref "P1") (pin "J8") (pinfunction "J8_J8") (pintype "passive"))
      (node (ref "P1") (pin "K12") (pinfunction "K12_K12") (pintype "passive"))
      (node (ref "P1") (pin "K15") (pinfunction "K15_K15") (pintype "passive"))
      (node (ref "P1") (pin "K18") (pinfunction "K18_K18") (pintype "passive"))
      (node (ref "P1") (pin "K2") (pinfunction "K2_K2") (pintype "passive"))
      (node (ref "P1") (pin "K21") (pinfunction "K21_K21") (pintype "passive"))
      (node (ref "P1") (pin "K24") (pinfunction "K24_K24") (pintype "passive"))
      (node (ref "P1") (pin "K27") (pinfunction "K27_K27") (pintype "passive"))
      (node (ref "P1") (pin "K3") (pinfunction "K3_K3") (pintype "passive"))
      (node (ref "P1") (pin "K30") (pinfunction "K30_K30") (pintype "passive"))
      (node (ref "P1") (pin "K33") (pinfunction "K33_K33") (pintype "passive"))
      (node (ref "P1") (pin "K36") (pinfunction "K36_K36") (pintype "passive"))
      (node (ref "P1") (pin "K39") (pinfunction "K39_K39") (pintype "passive"))
      (node (ref "P1") (pin "K6") (pinfunction "K6_K6") (pintype "passive"))
      (node (ref "P1") (pin "K9") (pinfunction "K9_K9") (pintype "passive"))
    )
    (net (code "249") (name "VCC_3p3_HOST") (class "Default")
      (node (ref "P1") (pin "C39") (pinfunction "C39_C39") (pintype "passive"))
      (node (ref "P1") (pin "D36") (pinfunction "D36_D36") (pintype "passive"))
      (node (ref "P1") (pin "D38") (pinfunction "D38_D38") (pintype "passive"))
      (node (ref "P1") (pin "D40") (pinfunction "D40_D40") (pintype "passive"))
    )
    (net (code "250") (name "VCC_12p0_HOST") (class "Default")
      (node (ref "P1") (pin "C35") (pinfunction "C35_C35") (pintype "passive"))
      (node (ref "P1") (pin "C37") (pinfunction "C37_C37") (pintype "passive"))
    )
    (net (code "251") (name "VCC_VADJ_CARD") (class "Default")
      (node (ref "P1") (pin "E39") (pinfunction "E39_E39") (pintype "passive"))
      (node (ref "P1") (pin "F40") (pinfunction "F40_F40") (pintype "passive"))
      (node (ref "P1") (pin "G39") (pinfunction "G39_G39") (pintype "passive"))
      (node (ref "P1") (pin "H40") (pinfunction "H40_H40") (pintype "passive"))
    )
    (net (code "252") (name "unconnected-(P1-PadB20)") (class "Default")
      (node (ref "P1") (pin "B20") (pinfunction "B20_B20") (pintype "passive"))
    )
    (net (code "253") (name "unconnected-(P1-PadB21)") (class "Default")
      (node (ref "P1") (pin "B21") (pinfunction "B21_B21") (pintype "passive"))
    )
    (net (code "254") (name "unconnected-(P1-PadB40)") (class "Default")
      (node (ref "P1") (pin "B40") (pinfunction "B40_B40") (pintype "passive+no_connect"))
    )
  )
)
